# SCH_A320-MCDU-SMD_2024-02-10.net
KiCad netlist of a schematic drawn in EasyEDA
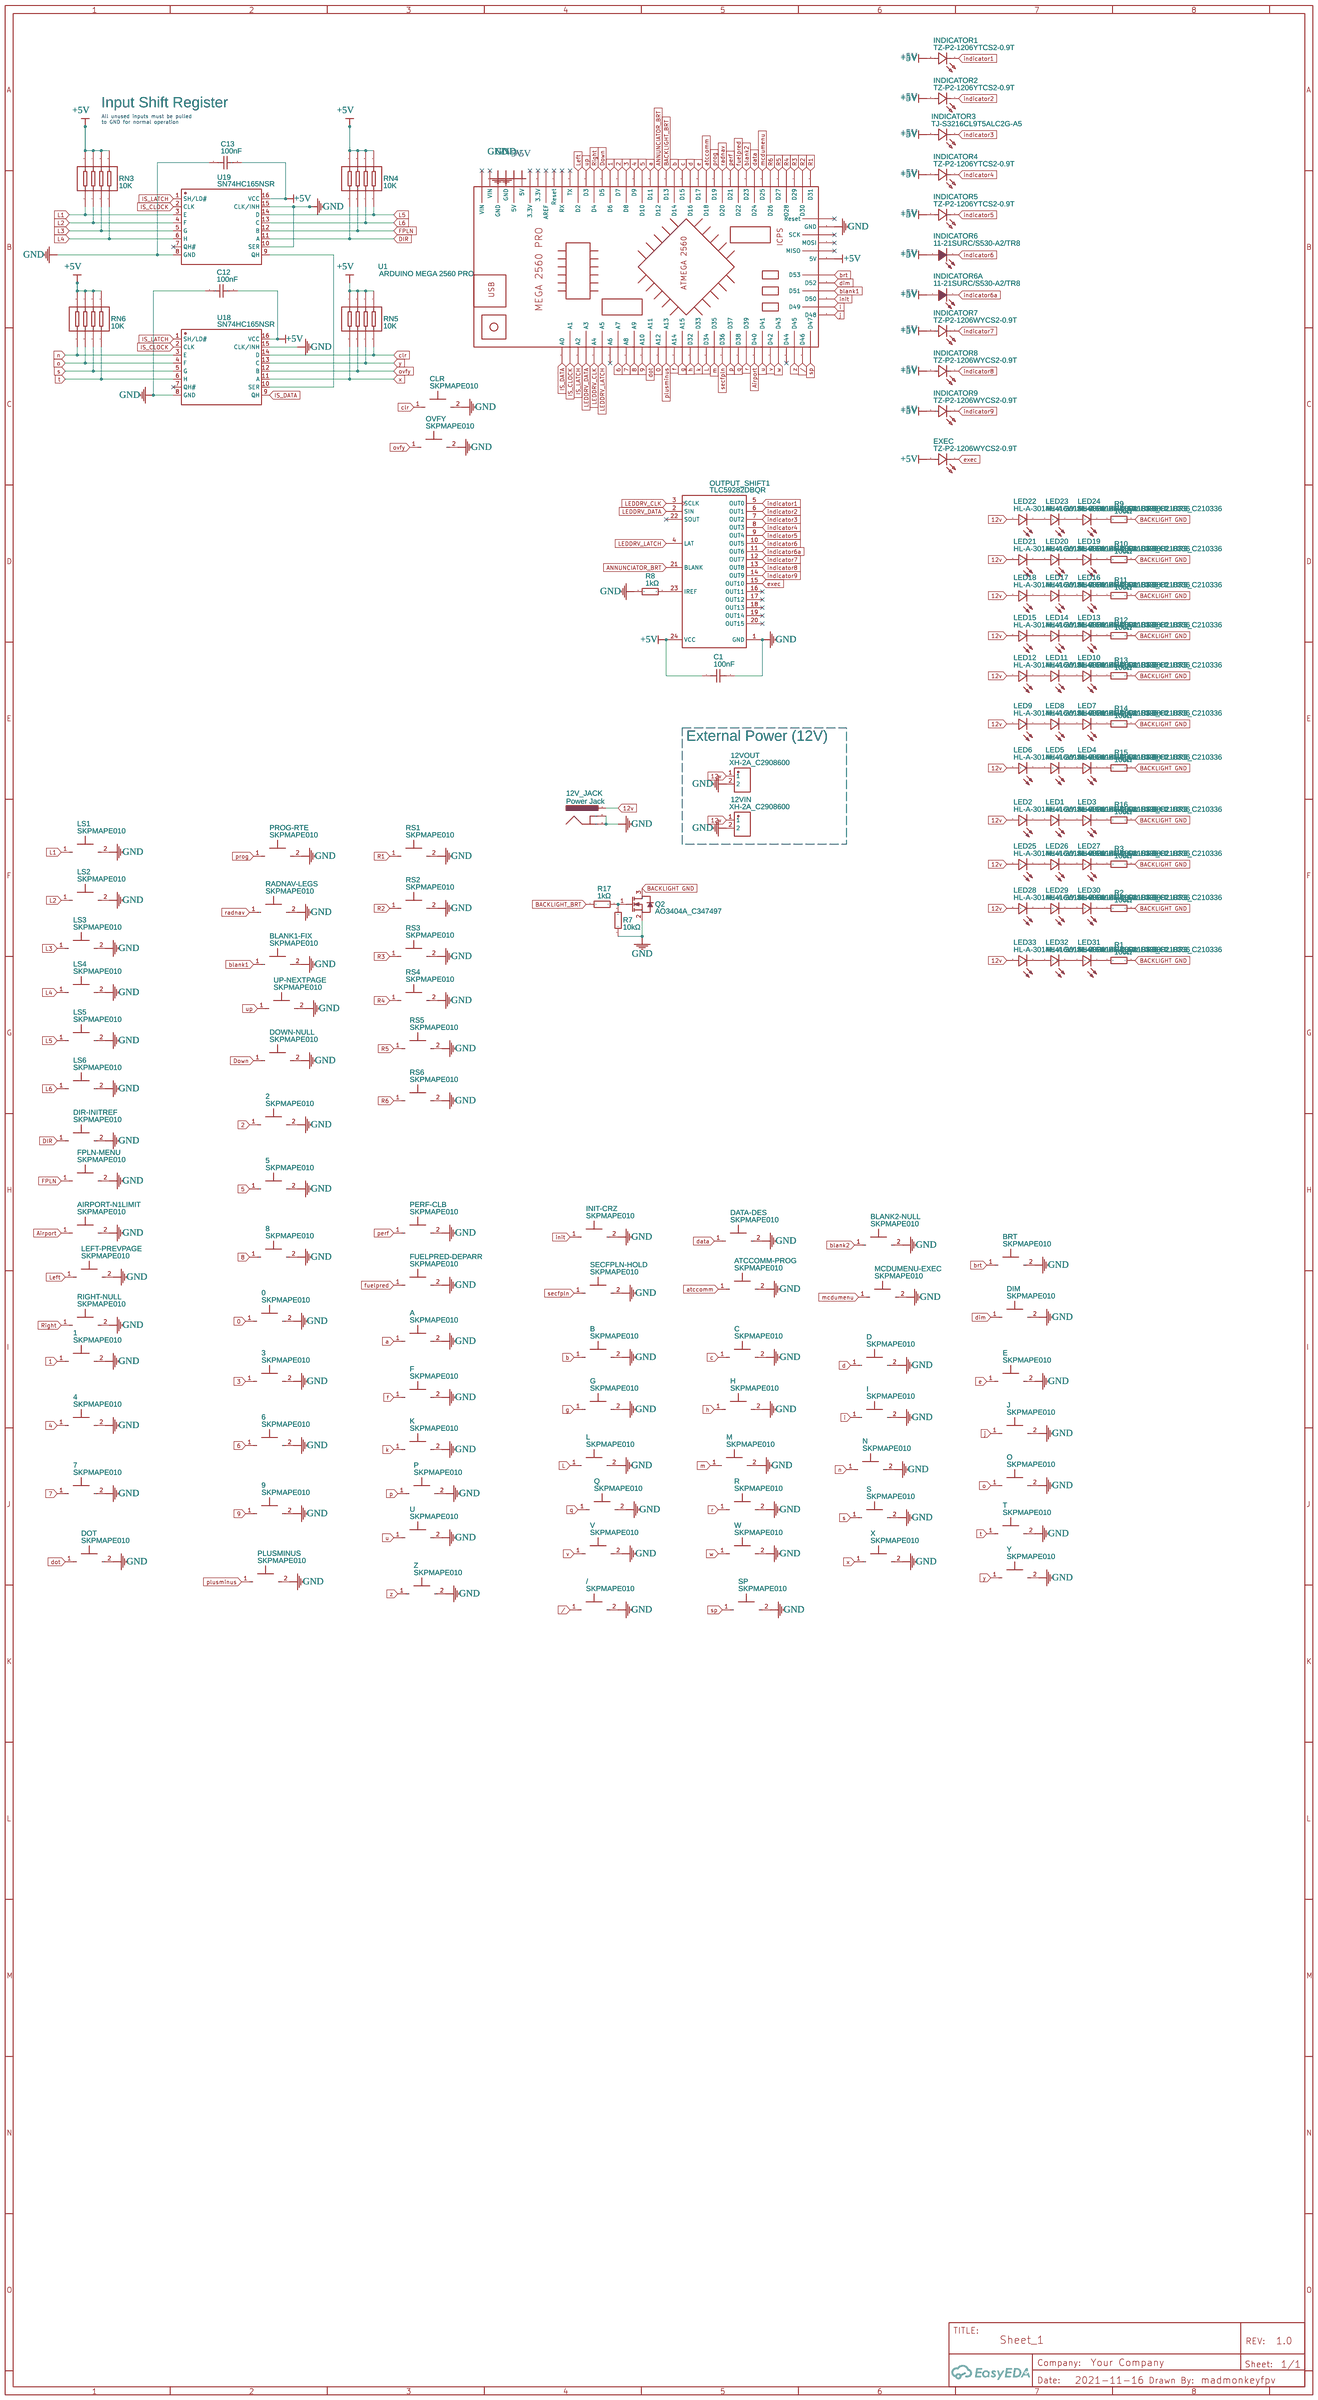
[diagram p0: schematic sheet]

(export (version "E")
  (design (tool "Eeschema 10.0.6"))
  (components
    (comp (ref "/")
      (value "SKPMAPE010")
      (fields (field (name "Manufacturer") "ALPS"))
      (libsource (lib "") (part "SKPMAPE010_46"))
    )
    (comp (ref "0")
      (value "SKPMAPE010")
      (fields (field (name "Manufacturer") "ALPS"))
      (libsource (lib "") (part "SKPMAPE010_12"))
    )
    (comp (ref "1")
      (value "SKPMAPE010")
      (fields (field (name "Manufacturer") "ALPS"))
      (libsource (lib "") (part "SKPMAPE010_12"))
    )
    (comp (ref "2")
      (value "SKPMAPE010")
      (fields (field (name "Manufacturer") "ALPS"))
      (libsource (lib "") (part "SKPMAPE010_12"))
    )
    (comp (ref "3")
      (value "SKPMAPE010")
      (fields (field (name "Manufacturer") "ALPS"))
      (libsource (lib "") (part "SKPMAPE010_12"))
    )
    (comp (ref "4")
      (value "SKPMAPE010")
      (fields (field (name "Manufacturer") "ALPS"))
      (libsource (lib "") (part "SKPMAPE010_12"))
    )
    (comp (ref "5")
      (value "SKPMAPE010")
      (fields (field (name "Manufacturer") "ALPS"))
      (libsource (lib "") (part "SKPMAPE010_12"))
    )
    (comp (ref "6")
      (value "SKPMAPE010")
      (fields (field (name "Manufacturer") "ALPS"))
      (libsource (lib "") (part "SKPMAPE010_12"))
    )
    (comp (ref "7")
      (value "SKPMAPE010")
      (fields (field (name "Manufacturer") "ALPS"))
      (libsource (lib "") (part "SKPMAPE010_12"))
    )
    (comp (ref "8")
      (value "SKPMAPE010")
      (fields (field (name "Manufacturer") "ALPS"))
      (libsource (lib "") (part "SKPMAPE010_12"))
    )
    (comp (ref "9")
      (value "SKPMAPE010")
      (fields (field (name "Manufacturer") "ALPS"))
      (libsource (lib "") (part "SKPMAPE010_12"))
    )
    (comp (ref "12VIN")
      (value "XH-2A_C2908600")
      (fields (field (name "Manufacturer Part") "XH-2A") (field (name "Manufacturer") "HCTL(华灿天禄)"))
      (libsource (lib "") (part "XH-2A_C2908600_1"))
    )
    (comp (ref "12VOUT")
      (value "XH-2A_C2908600")
      (fields (field (name "Manufacturer Part") "XH-2A") (field (name "Manufacturer") "HCTL(华灿天禄)"))
      (libsource (lib "") (part "XH-2A_C2908600"))
    )
    (comp (ref "12V_JACK")
      (value "Power Jack")
      (fields (field (name "Manufacturer") "Wealth Metal"))
      (libsource (lib "") (part "POWER_JACK"))
    )
    (comp (ref "A")
      (value "SKPMAPE010")
      (fields (field (name "Manufacturer Part") "KSC241JLFS") (field (name "Manufacturer") "C&K"))
      (libsource (lib "") (part "Unknown_0_-806"))
    )
    (comp (ref "AIRPORT-N1LIMIT")
      (value "SKPMAPE010")
      (fields (field (name "Manufacturer") "ALPS"))
      (libsource (lib "") (part "SKPMAPE010_50"))
    )
    (comp (ref "ATCCOMM-PROG")
      (value "SKPMAPE010")
      (fields (field (name "Manufacturer") "ALPS"))
      (libsource (lib "") (part "SKPMAPE010_43"))
    )
    (comp (ref "B")
      (value "SKPMAPE010")
      (fields (field (name "Manufacturer") "ALPS"))
      (libsource (lib "") (part "SKPMAPE010_31"))
    )
    (comp (ref "BLANK1-FIX")
      (value "SKPMAPE010")
      (fields (field (name "Manufacturer") "ALPS"))
      (libsource (lib "") (part "SKPMAPE010_4"))
    )
    (comp (ref "BLANK2-NULL")
      (value "SKPMAPE010")
      (fields (field (name "Manufacturer") "ALPS"))
      (libsource (lib "") (part "SKPMAPE010_39"))
    )
    (comp (ref "BRT")
      (value "SKPMAPE010")
      (fields (field (name "Manufacturer") "ALPS"))
      (libsource (lib "") (part "SKPMAPE010_25"))
    )
    (comp (ref "C")
      (value "SKPMAPE010")
      (fields (field (name "Manufacturer") "ALPS"))
      (libsource (lib "") (part "SKPMAPE010_40"))
    )
    (comp (ref "C1")
      (value "100nF")
      (fields (field (name "Manufacturer Part") "CC0603KRX7R9BB104") (field (name "Manufacturer") "YAGEO"))
      (libsource (lib "") (part "CC0603KRX7R9BB104"))
    )
    (comp (ref "C12")
      (value "100nF")
      (fields (field (name "Manufacturer Part") "CC0603KRX7R9BB104") (field (name "Manufacturer") "YAGEO"))
      (libsource (lib "") (part "CC0603KRX7R9BB104"))
    )
    (comp (ref "C13")
      (value "100nF")
      (fields (field (name "Manufacturer Part") "CC0603KRX7R9BB104") (field (name "Manufacturer") "YAGEO"))
      (libsource (lib "") (part "CC0603KRX7R9BB104"))
    )
    (comp (ref "CLR")
      (value "SKPMAPE010")
      (fields (field (name "Manufacturer") "ALPS"))
      (libsource (lib "") (part "SKPMAPE010_34"))
    )
    (comp (ref "D")
      (value "SKPMAPE010")
      (fields (field (name "Manufacturer") "ALPS"))
      (libsource (lib "") (part "SKPMAPE010_32"))
    )
    (comp (ref "DATA-DES")
      (value "SKPMAPE010")
      (fields (field (name "Manufacturer") "ALPS"))
      (libsource (lib "") (part "SKPMAPE010_22"))
    )
    (comp (ref "DIM")
      (value "SKPMAPE010")
      (fields (field (name "Manufacturer") "ALPS"))
      (libsource (lib "") (part "SKPMAPE010_42"))
    )
    (comp (ref "DIR-INITREF")
      (value "SKPMAPE010")
      (fields (field (name "Manufacturer") "ALPS"))
      (libsource (lib "") (part "SKPMAPE010_14"))
    )
    (comp (ref "DOT")
      (value "SKPMAPE010")
      (fields (field (name "Manufacturer") "ALPS"))
      (libsource (lib "") (part "SKPMAPE010_2"))
    )
    (comp (ref "DOWN-NULL")
      (value "SKPMAPE010")
      (fields (field (name "Manufacturer") "ALPS"))
      (libsource (lib "") (part "SKPMAPE010_21"))
    )
    (comp (ref "E")
      (value "SKPMAPE010")
      (fields (field (name "Manufacturer") "ALPS"))
      (libsource (lib "") (part "SKPMAPE010_17"))
    )
    (comp (ref "EXEC")
      (value "TZ-P2-1206WYCS2-0.9T")
      (fields (field (name "Manufacturer") "TUOZHAN"))
      (libsource (lib "") (part "TZ-P2-1206WYCS2-0.9T"))
    )
    (comp (ref "F")
      (value "SKPMAPE010")
      (fields (field (name "Manufacturer") "ALPS"))
      (libsource (lib "") (part "SKPMAPE010_27"))
    )
    (comp (ref "FPLN-MENU")
      (value "SKPMAPE010")
      (fields (field (name "Manufacturer") "ALPS"))
      (libsource (lib "") (part "SKPMAPE010_20"))
    )
    (comp (ref "FUELPRED-DEPARR")
      (value "SKPMAPE010")
      (fields (field (name "Manufacturer") "ALPS"))
      (libsource (lib "") (part "SKPMAPE010_1"))
    )
    (comp (ref "G")
      (value "SKPMAPE010")
      (fields (field (name "Manufacturer") "ALPS"))
      (libsource (lib "") (part "SKPMAPE010_49"))
    )
    (comp (ref "H")
      (value "SKPMAPE010")
      (fields (field (name "Manufacturer") "ALPS"))
      (libsource (lib "") (part "SKPMAPE010_19"))
    )
    (comp (ref "I")
      (value "SKPMAPE010")
      (fields (field (name "Manufacturer") "ALPS"))
      (libsource (lib "") (part "SKPMAPE010_47"))
    )
    (comp (ref "INDICATOR1")
      (value "TZ-P2-1206YTCS2-0.9T")
      (fields (field (name "Manufacturer") "TUOZHAN"))
      (libsource (lib "") (part "TZ-P2-1206YTCS2-0.9T"))
    )
    (comp (ref "INDICATOR2")
      (value "TZ-P2-1206YTCS2-0.9T")
      (fields (field (name "Manufacturer") "TUOZHAN"))
      (libsource (lib "") (part "TZ-P2-1206YTCS2-0.9T"))
    )
    (comp (ref "INDICATOR3")
      (value "TJ-S3216CL9T5ALC2G-A5")
      (fields (field (name "Manufacturer") "TOGIALED"))
      (libsource (lib "") (part "TJ-S3216CL9T5ALC2G-A5"))
    )
    (comp (ref "INDICATOR4")
      (value "TZ-P2-1206YTCS2-0.9T")
      (fields (field (name "Manufacturer") "TUOZHAN"))
      (libsource (lib "") (part "TZ-P2-1206YTCS2-0.9T"))
    )
    (comp (ref "INDICATOR5")
      (value "TZ-P2-1206YTCS2-0.9T")
      (fields (field (name "Manufacturer") "TUOZHAN"))
      (libsource (lib "") (part "TZ-P2-1206YTCS2-0.9T"))
    )
    (comp (ref "INDICATOR6")
      (value "11-21SURC/S530-A2/TR8")
      (fields (field (name "Manufacturer") "Everlight Elec"))
      (libsource (lib "") (part "11-21SURC/S530-A2/TR8"))
    )
    (comp (ref "INDICATOR6A")
      (value "11-21SURC/S530-A2/TR8")
      (fields (field (name "Manufacturer") "Everlight Elec"))
      (libsource (lib "") (part "11-21SURC/S530-A2/TR8_1"))
    )
    (comp (ref "INDICATOR7")
      (value "TZ-P2-1206WYCS2-0.9T")
      (fields (field (name "Manufacturer") "TUOZHAN"))
      (libsource (lib "") (part "TZ-P2-1206WYCS2-0.9T_1"))
    )
    (comp (ref "INDICATOR8")
      (value "TZ-P2-1206WYCS2-0.9T")
      (fields (field (name "Manufacturer") "TUOZHAN"))
      (libsource (lib "") (part "TZ-P2-1206WYCS2-0.9T_1"))
    )
    (comp (ref "INDICATOR9")
      (value "TZ-P2-1206WYCS2-0.9T")
      (fields (field (name "Manufacturer") "TUOZHAN"))
      (libsource (lib "") (part "TZ-P2-1206WYCS2-0.9T_1"))
    )
    (comp (ref "INIT-CRZ")
      (value "SKPMAPE010")
      (fields (field (name "Manufacturer") "ALPS"))
      (libsource (lib "") (part "SKPMAPE010_7"))
    )
    (comp (ref "J")
      (value "SKPMAPE010")
      (fields (field (name "Manufacturer") "ALPS"))
      (libsource (lib "") (part "SKPMAPE010_37"))
    )
    (comp (ref "K")
      (value "SKPMAPE010")
      (fields (field (name "Manufacturer") "ALPS"))
      (libsource (lib "") (part "SKPMAPE010_8"))
    )
    (comp (ref "L")
      (value "SKPMAPE010")
      (fields (field (name "Manufacturer") "ALPS"))
      (libsource (lib "") (part "SKPMAPE010_48"))
    )
    (comp (ref "LED1")
      (value "HL-A-3014H416W-S1-08HL-HR3_C210336")
      (fields (field (name "Manufacturer") "Hongli Zhihui (HONGLITRONIC)"))
      (libsource (lib "") (part "HL-A-3014H416W-S1-08HL-HR3_C210336"))
    )
    (comp (ref "LED2")
      (value "HL-A-3014H416W-S1-08HL-HR3_C210336")
      (fields (field (name "Manufacturer") "Hongli Zhihui (HONGLITRONIC)"))
      (libsource (lib "") (part "HL-A-3014H416W-S1-08HL-HR3_C210336"))
    )
    (comp (ref "LED3")
      (value "HL-A-3014H416W-S1-08HL-HR3_C210336")
      (fields (field (name "Manufacturer") "Hongli Zhihui (HONGLITRONIC)"))
      (libsource (lib "") (part "HL-A-3014H416W-S1-08HL-HR3_C210336"))
    )
    (comp (ref "LED4")
      (value "HL-A-3014H416W-S1-08HL-HR3_C210336")
      (fields (field (name "Manufacturer") "Hongli Zhihui (HONGLITRONIC)"))
      (libsource (lib "") (part "HL-A-3014H416W-S1-08HL-HR3_C210336"))
    )
    (comp (ref "LED5")
      (value "HL-A-3014H416W-S1-08HL-HR3_C210336")
      (fields (field (name "Manufacturer") "Hongli Zhihui (HONGLITRONIC)"))
      (libsource (lib "") (part "HL-A-3014H416W-S1-08HL-HR3_C210336"))
    )
    (comp (ref "LED6")
      (value "HL-A-3014H416W-S1-08HL-HR3_C210336")
      (fields (field (name "Manufacturer") "Hongli Zhihui (HONGLITRONIC)"))
      (libsource (lib "") (part "HL-A-3014H416W-S1-08HL-HR3_C210336"))
    )
    (comp (ref "LED7")
      (value "HL-A-3014H416W-S1-08HL-HR3_C210336")
      (fields (field (name "Manufacturer") "Hongli Zhihui (HONGLITRONIC)"))
      (libsource (lib "") (part "HL-A-3014H416W-S1-08HL-HR3_C210336"))
    )
    (comp (ref "LED8")
      (value "HL-A-3014H416W-S1-08HL-HR3_C210336")
      (fields (field (name "Manufacturer") "Hongli Zhihui (HONGLITRONIC)"))
      (libsource (lib "") (part "HL-A-3014H416W-S1-08HL-HR3_C210336"))
    )
    (comp (ref "LED9")
      (value "HL-A-3014H416W-S1-08HL-HR3_C210336")
      (fields (field (name "Manufacturer") "Hongli Zhihui (HONGLITRONIC)"))
      (libsource (lib "") (part "HL-A-3014H416W-S1-08HL-HR3_C210336"))
    )
    (comp (ref "LED10")
      (value "HL-A-3014H416W-S1-08HL-HR3_C210336")
      (fields (field (name "Manufacturer") "Hongli Zhihui (HONGLITRONIC)"))
      (libsource (lib "") (part "HL-A-3014H416W-S1-08HL-HR3_C210336"))
    )
    (comp (ref "LED11")
      (value "HL-A-3014H416W-S1-08HL-HR3_C210336")
      (fields (field (name "Manufacturer") "Hongli Zhihui (HONGLITRONIC)"))
      (libsource (lib "") (part "HL-A-3014H416W-S1-08HL-HR3_C210336"))
    )
    (comp (ref "LED12")
      (value "HL-A-3014H416W-S1-08HL-HR3_C210336")
      (fields (field (name "Manufacturer") "Hongli Zhihui (HONGLITRONIC)"))
      (libsource (lib "") (part "HL-A-3014H416W-S1-08HL-HR3_C210336"))
    )
    (comp (ref "LED13")
      (value "HL-A-3014H416W-S1-08HL-HR3_C210336")
      (fields (field (name "Manufacturer") "Hongli Zhihui (HONGLITRONIC)"))
      (libsource (lib "") (part "HL-A-3014H416W-S1-08HL-HR3_C210336"))
    )
    (comp (ref "LED14")
      (value "HL-A-3014H416W-S1-08HL-HR3_C210336")
      (fields (field (name "Manufacturer") "Hongli Zhihui (HONGLITRONIC)"))
      (libsource (lib "") (part "HL-A-3014H416W-S1-08HL-HR3_C210336"))
    )
    (comp (ref "LED15")
      (value "HL-A-3014H416W-S1-08HL-HR3_C210336")
      (fields (field (name "Manufacturer") "Hongli Zhihui (HONGLITRONIC)"))
      (libsource (lib "") (part "HL-A-3014H416W-S1-08HL-HR3_C210336"))
    )
    (comp (ref "LED16")
      (value "HL-A-3014H416W-S1-08HL-HR3_C210336")
      (fields (field (name "Manufacturer") "Hongli Zhihui (HONGLITRONIC)"))
      (libsource (lib "") (part "HL-A-3014H416W-S1-08HL-HR3_C210336"))
    )
    (comp (ref "LED17")
      (value "HL-A-3014H416W-S1-08HL-HR3_C210336")
      (fields (field (name "Manufacturer") "Hongli Zhihui (HONGLITRONIC)"))
      (libsource (lib "") (part "HL-A-3014H416W-S1-08HL-HR3_C210336"))
    )
    (comp (ref "LED18")
      (value "HL-A-3014H416W-S1-08HL-HR3_C210336")
      (fields (field (name "Manufacturer") "Hongli Zhihui (HONGLITRONIC)"))
      (libsource (lib "") (part "HL-A-3014H416W-S1-08HL-HR3_C210336"))
    )
    (comp (ref "LED19")
      (value "HL-A-3014H416W-S1-08HL-HR3_C210336")
      (fields (field (name "Manufacturer") "Hongli Zhihui (HONGLITRONIC)"))
      (libsource (lib "") (part "HL-A-3014H416W-S1-08HL-HR3_C210336"))
    )
    (comp (ref "LED20")
      (value "HL-A-3014H416W-S1-08HL-HR3_C210336")
      (fields (field (name "Manufacturer") "Hongli Zhihui (HONGLITRONIC)"))
      (libsource (lib "") (part "HL-A-3014H416W-S1-08HL-HR3_C210336"))
    )
    (comp (ref "LED21")
      (value "HL-A-3014H416W-S1-08HL-HR3_C210336")
      (fields (field (name "Manufacturer") "Hongli Zhihui (HONGLITRONIC)"))
      (libsource (lib "") (part "HL-A-3014H416W-S1-08HL-HR3_C210336"))
    )
    (comp (ref "LED22")
      (value "HL-A-3014H416W-S1-08HL-HR3_C210336")
      (fields (field (name "Manufacturer") "Hongli Zhihui (HONGLITRONIC)"))
      (libsource (lib "") (part "HL-A-3014H416W-S1-08HL-HR3_C210336"))
    )
    (comp (ref "LED23")
      (value "HL-A-3014H416W-S1-08HL-HR3_C210336")
      (fields (field (name "Manufacturer") "Hongli Zhihui (HONGLITRONIC)"))
      (libsource (lib "") (part "HL-A-3014H416W-S1-08HL-HR3_C210336"))
    )
    (comp (ref "LED24")
      (value "HL-A-3014H416W-S1-08HL-HR3_C210336")
      (fields (field (name "Manufacturer") "Hongli Zhihui (HONGLITRONIC)"))
      (libsource (lib "") (part "HL-A-3014H416W-S1-08HL-HR3_C210336"))
    )
    (comp (ref "LED25")
      (value "HL-A-3014H416W-S1-08HL-HR3_C210336")
      (fields (field (name "Manufacturer") "Hongli Zhihui (HONGLITRONIC)"))
      (libsource (lib "") (part "HL-A-3014H416W-S1-08HL-HR3_C210336"))
    )
    (comp (ref "LED26")
      (value "HL-A-3014H416W-S1-08HL-HR3_C210336")
      (fields (field (name "Manufacturer") "Hongli Zhihui (HONGLITRONIC)"))
      (libsource (lib "") (part "HL-A-3014H416W-S1-08HL-HR3_C210336"))
    )
    (comp (ref "LED27")
      (value "HL-A-3014H416W-S1-08HL-HR3_C210336")
      (fields (field (name "Manufacturer") "Hongli Zhihui (HONGLITRONIC)"))
      (libsource (lib "") (part "HL-A-3014H416W-S1-08HL-HR3_C210336"))
    )
    (comp (ref "LED28")
      (value "HL-A-3014H416W-S1-08HL-HR3_C210336")
      (fields (field (name "Manufacturer") "Hongli Zhihui (HONGLITRONIC)"))
      (libsource (lib "") (part "HL-A-3014H416W-S1-08HL-HR3_C210336"))
    )
    (comp (ref "LED29")
      (value "HL-A-3014H416W-S1-08HL-HR3_C210336")
      (fields (field (name "Manufacturer") "Hongli Zhihui (HONGLITRONIC)"))
      (libsource (lib "") (part "HL-A-3014H416W-S1-08HL-HR3_C210336"))
    )
    (comp (ref "LED30")
      (value "HL-A-3014H416W-S1-08HL-HR3_C210336")
      (fields (field (name "Manufacturer") "Hongli Zhihui (HONGLITRONIC)"))
      (libsource (lib "") (part "HL-A-3014H416W-S1-08HL-HR3_C210336"))
    )
    (comp (ref "LED31")
      (value "HL-A-3014H416W-S1-08HL-HR3_C210336")
      (fields (field (name "Manufacturer") "Hongli Zhihui (HONGLITRONIC)"))
      (libsource (lib "") (part "HL-A-3014H416W-S1-08HL-HR3_C210336"))
    )
    (comp (ref "LED32")
      (value "HL-A-3014H416W-S1-08HL-HR3_C210336")
      (fields (field (name "Manufacturer") "Hongli Zhihui (HONGLITRONIC)"))
      (libsource (lib "") (part "HL-A-3014H416W-S1-08HL-HR3_C210336"))
    )
    (comp (ref "LED33")
      (value "HL-A-3014H416W-S1-08HL-HR3_C210336")
      (fields (field (name "Manufacturer") "Hongli Zhihui (HONGLITRONIC)"))
      (libsource (lib "") (part "HL-A-3014H416W-S1-08HL-HR3_C210336"))
    )
    (comp (ref "LEFT-PREVPAGE")
      (value "SKPMAPE010")
      (fields (field (name "Manufacturer") "ALPS"))
      (libsource (lib "") (part "SKPMAPE010_36"))
    )
    (comp (ref "LS1")
      (value "SKPMAPE010")
      (fields (field (name "Manufacturer") "ALPS"))
      (libsource (lib "") (part "SKPMAPE010_16"))
    )
    (comp (ref "LS2")
      (value "SKPMAPE010")
      (fields (field (name "Manufacturer") "ALPS"))
      (libsource (lib "") (part "SKPMAPE010_16"))
    )
    (comp (ref "LS3")
      (value "SKPMAPE010")
      (fields (field (name "Manufacturer") "ALPS"))
      (libsource (lib "") (part "SKPMAPE010_16"))
    )
    (comp (ref "LS4")
      (value "SKPMAPE010")
      (fields (field (name "Manufacturer") "ALPS"))
      (libsource (lib "") (part "SKPMAPE010_16"))
    )
    (comp (ref "LS5")
      (value "SKPMAPE010")
      (fields (field (name "Manufacturer") "ALPS"))
      (libsource (lib "") (part "SKPMAPE010_16"))
    )
    (comp (ref "LS6")
      (value "SKPMAPE010")
      (fields (field (name "Manufacturer") "ALPS"))
      (libsource (lib "") (part "SKPMAPE010_16"))
    )
    (comp (ref "M")
      (value "SKPMAPE010")
      (fields (field (name "Manufacturer") "ALPS"))
      (libsource (lib "") (part "SKPMAPE010_11"))
    )
    (comp (ref "MCDUMENU-EXEC")
      (value "SKPMAPE010")
      (fields (field (name "Manufacturer") "ALPS"))
      (libsource (lib "") (part "SKPMAPE010_44"))
    )
    (comp (ref "N")
      (value "SKPMAPE010")
      (fields (field (name "Manufacturer") "ALPS"))
      (libsource (lib "") (part "SKPMAPE010_18"))
    )
    (comp (ref "O")
      (value "SKPMAPE010")
      (fields (field (name "Manufacturer") "ALPS"))
      (libsource (lib "") (part "SKPMAPE010_51"))
    )
    (comp (ref "OUTPUT_SHIFT1")
      (value "TLC59282DBQR")
      (fields (field (name "Manufacturer") "TI(德州仪器)"))
      (libsource (lib "") (part "TLC59282DBQR"))
    )
    (comp (ref "OVFY")
      (value "SKPMAPE010")
      (fields (field (name "Manufacturer") "ALPS"))
      (libsource (lib "") (part "SKPMAPE010"))
    )
    (comp (ref "P")
      (value "SKPMAPE010")
      (fields (field (name "Manufacturer") "ALPS"))
      (libsource (lib "") (part "SKPMAPE010_38"))
    )
    (comp (ref "PERF-CLB")
      (value "SKPMAPE010")
      (fields (field (name "Manufacturer") "ALPS"))
      (libsource (lib "") (part "SKPMAPE010_10"))
    )
    (comp (ref "PLUSMINUS")
      (value "SKPMAPE010")
      (fields (field (name "Manufacturer") "ALPS"))
      (libsource (lib "") (part "SKPMAPE010_33"))
    )
    (comp (ref "PROG-RTE")
      (value "SKPMAPE010")
      (fields (field (name "Manufacturer") "ALPS"))
      (libsource (lib "") (part "SKPMAPE010_3"))
    )
    (comp (ref "Q")
      (value "SKPMAPE010")
      (fields (field (name "Manufacturer") "ALPS"))
      (libsource (lib "") (part "SKPMAPE010_45"))
    )
    (comp (ref "Q2")
      (value "AO3404A_C347497")
      (fields
        (field (name "Manufacturer Part") "AO3404A")
        (field (name "Manufacturer") "Youtai Semiconductor Co., Ltd.")
      )
      (libsource (lib "") (part "AO3404A_C347497"))
    )
    (comp (ref "R")
      (value "SKPMAPE010")
      (fields (field (name "Manufacturer") "ALPS"))
      (libsource (lib "") (part "SKPMAPE010_29"))
    )
    (comp (ref "R1")
      (value "100Ω")
      (fields (field (name "Manufacturer Part") "1206W4F1000T5E") (field (name "Manufacturer") "UniOhm"))
      (libsource (lib "") (part "1206W4F1000T5E"))
    )
    (comp (ref "R2")
      (value "100Ω")
      (fields (field (name "Manufacturer Part") "1206W4F1000T5E") (field (name "Manufacturer") "UniOhm"))
      (libsource (lib "") (part "1206W4F1000T5E"))
    )
    (comp (ref "R3")
      (value "100Ω")
      (fields (field (name "Manufacturer Part") "1206W4F1000T5E") (field (name "Manufacturer") "UniOhm"))
      (libsource (lib "") (part "1206W4F1000T5E"))
    )
    (comp (ref "R7")
      (value "10kΩ")
      (fields (field (name "Manufacturer Part") "1206W4F1002T5E") (field (name "Manufacturer") "UniOhm"))
      (libsource (lib "") (part "1206W4F1002T5E"))
    )
    (comp (ref "R8")
      (value "1kΩ")
      (fields (field (name "Manufacturer Part") "1206W4F1001T5E") (field (name "Manufacturer") "UniOhm"))
      (libsource (lib "") (part "1206W4F1001T5E"))
    )
    (comp (ref "R9")
      (value "100Ω")
      (fields (field (name "Manufacturer Part") "1206W4F1000T5E") (field (name "Manufacturer") "UniOhm"))
      (libsource (lib "") (part "1206W4F1000T5E"))
    )
    (comp (ref "R10")
      (value "100Ω")
      (fields (field (name "Manufacturer Part") "1206W4F1000T5E") (field (name "Manufacturer") "UniOhm"))
      (libsource (lib "") (part "1206W4F1000T5E"))
    )
    (comp (ref "R11")
      (value "100Ω")
      (fields (field (name "Manufacturer Part") "1206W4F1000T5E") (field (name "Manufacturer") "UniOhm"))
      (libsource (lib "") (part "1206W4F1000T5E"))
    )
    (comp (ref "R12")
      (value "100Ω")
      (fields (field (name "Manufacturer Part") "1206W4F1000T5E") (field (name "Manufacturer") "UniOhm"))
      (libsource (lib "") (part "1206W4F1000T5E"))
    )
    (comp (ref "R13")
      (value "100Ω")
      (fields (field (name "Manufacturer Part") "1206W4F1000T5E") (field (name "Manufacturer") "UniOhm"))
      (libsource (lib "") (part "1206W4F1000T5E"))
    )
    (comp (ref "R14")
      (value "100Ω")
      (fields (field (name "Manufacturer Part") "1206W4F1000T5E") (field (name "Manufacturer") "UniOhm"))
      (libsource (lib "") (part "1206W4F1000T5E"))
    )
    (comp (ref "R15")
      (value "100Ω")
      (fields (field (name "Manufacturer Part") "1206W4F1000T5E") (field (name "Manufacturer") "UniOhm"))
      (libsource (lib "") (part "1206W4F1000T5E"))
    )
    (comp (ref "R16")
      (value "100Ω")
      (fields (field (name "Manufacturer Part") "1206W4F1000T5E") (field (name "Manufacturer") "UniOhm"))
      (libsource (lib "") (part "1206W4F1000T5E"))
    )
    (comp (ref "R17")
      (value "1kΩ")
      (fields (field (name "Manufacturer Part") "1206W4F1001T5E") (field (name "Manufacturer") "UniOhm"))
      (libsource (lib "") (part "1206W4F1001T5E_1"))
    )
    (comp (ref "RADNAV-LEGS")
      (value "SKPMAPE010")
      (fields (field (name "Manufacturer") "ALPS"))
      (libsource (lib "") (part "SKPMAPE010_41"))
    )
    (comp (ref "RIGHT-NULL")
      (value "SKPMAPE010")
      (fields (field (name "Manufacturer") "ALPS"))
      (libsource (lib "") (part "SKPMAPE010_15"))
    )
    (comp (ref "RN3")
      (value "10K")
      (fields (field (name "Manufacturer Part") "YC164-FR-0710KL") (field (name "Manufacturer") "YAGEO"))
      (libsource (lib "") (part "YC164-FR-0710KL"))
    )
    (comp (ref "RN4")
      (value "10K")
      (fields (field (name "Manufacturer Part") "YC164-FR-0710KL") (field (name "Manufacturer") "YAGEO"))
      (libsource (lib "") (part "YC164-FR-0710KL_1"))
    )
    (comp (ref "RN5")
      (value "10K")
      (fields (field (name "Manufacturer Part") "YC164-FR-0710KL") (field (name "Manufacturer") "YAGEO"))
      (libsource (lib "") (part "YC164-FR-0710KL_1"))
    )
    (comp (ref "RN6")
      (value "10K")
      (fields (field (name "Manufacturer Part") "YC164-FR-0710KL") (field (name "Manufacturer") "YAGEO"))
      (libsource (lib "") (part "YC164-FR-0710KL"))
    )
    (comp (ref "RS1")
      (value "SKPMAPE010")
      (fields (field (name "Manufacturer") "ALPS"))
      (libsource (lib "") (part "SKPMAPE010_9"))
    )
    (comp (ref "RS2")
      (value "SKPMAPE010")
      (fields (field (name "Manufacturer") "ALPS"))
      (libsource (lib "") (part "SKPMAPE010_9"))
    )
    (comp (ref "RS3")
      (value "SKPMAPE010")
      (fields (field (name "Manufacturer") "ALPS"))
      (libsource (lib "") (part "SKPMAPE010_9"))
    )
    (comp (ref "RS4")
      (value "SKPMAPE010")
      (fields (field (name "Manufacturer") "ALPS"))
      (libsource (lib "") (part "SKPMAPE010_9"))
    )
    (comp (ref "RS5")
      (value "SKPMAPE010")
      (fields (field (name "Manufacturer") "ALPS"))
      (libsource (lib "") (part "SKPMAPE010_9"))
    )
    (comp (ref "RS6")
      (value "SKPMAPE010")
      (fields (field (name "Manufacturer") "ALPS"))
      (libsource (lib "") (part "SKPMAPE010_9"))
    )
    (comp (ref "S")
      (value "SKPMAPE010")
      (fields (field (name "Manufacturer") "ALPS"))
      (libsource (lib "") (part "SKPMAPE010_5"))
    )
    (comp (ref "SECFPLN-HOLD")
      (value "SKPMAPE010")
      (fields (field (name "Manufacturer") "ALPS"))
      (libsource (lib "") (part "SKPMAPE010_52"))
    )
    (comp (ref "SP")
      (value "SKPMAPE010")
      (fields (field (name "Manufacturer") "ALPS"))
      (libsource (lib "") (part "SKPMAPE010_26"))
    )
    (comp (ref "T")
      (value "SKPMAPE010")
      (fields (field (name "Manufacturer") "ALPS"))
      (libsource (lib "") (part "SKPMAPE010_13"))
    )
    (comp (ref "U")
      (value "SKPMAPE010")
      (fields (field (name "Manufacturer") "ALPS"))
      (libsource (lib "") (part "SKPMAPE010_53"))
    )
    (comp (ref "U1")
      (value "ARDUINO MEGA 2560 PRO")
      (fields (field (name "Manufacturer Part") "Arduino Mega 2560 Pro Mini"))
      (libsource (lib "") (part "ARDUINO MEGA 2560 PRO"))
    )
    (comp (ref "U18")
      (value "SN74HC165NSR")
      (fields (field (name "Manufacturer") "TI"))
      (libsource (lib "") (part "SN74HC165NSR"))
    )
    (comp (ref "U19")
      (value "SN74HC165NSR")
      (fields (field (name "Manufacturer") "TI"))
      (libsource (lib "") (part "SN74HC165NSR"))
    )
    (comp (ref "UP-NEXTPAGE")
      (value "SKPMAPE010")
      (fields (field (name "Manufacturer") "ALPS"))
      (libsource (lib "") (part "SKPMAPE010_24"))
    )
    (comp (ref "V")
      (value "SKPMAPE010")
      (fields (field (name "Manufacturer") "ALPS"))
      (libsource (lib "") (part "SKPMAPE010_30"))
    )
    (comp (ref "W")
      (value "SKPMAPE010")
      (fields (field (name "Manufacturer") "ALPS"))
      (libsource (lib "") (part "SKPMAPE010_23"))
    )
    (comp (ref "X")
      (value "SKPMAPE010")
      (fields (field (name "Manufacturer") "ALPS"))
      (libsource (lib "") (part "SKPMAPE010_28"))
    )
    (comp (ref "Y")
      (value "SKPMAPE010")
      (fields (field (name "Manufacturer") "ALPS"))
      (libsource (lib "") (part "SKPMAPE010_6"))
    )
    (comp (ref "Z")
      (value "SKPMAPE010")
      (fields (field (name "Manufacturer") "ALPS"))
      (libsource (lib "") (part "SKPMAPE010_54"))
    )
  )
  (nets
    (net (code "1") (name "+5V") (class "Default")
      (node (ref "C1") (pin "1") (pinfunction "1_1") (pintype "unspecified"))
      (node (ref "C12") (pin "2") (pinfunction "2_2") (pintype "unspecified"))
      (node (ref "C13") (pin "2") (pinfunction "2_2") (pintype "unspecified"))
      (node (ref "EXEC") (pin "2") (pinfunction "A_2") (pintype "unspecified"))
      (node (ref "INDICATOR1") (pin "2") (pinfunction "A_2") (pintype "unspecified"))
      (node (ref "INDICATOR2") (pin "2") (pinfunction "A_2") (pintype "unspecified"))
      (node (ref "INDICATOR3") (pin "2") (pinfunction "A_2") (pintype "unspecified"))
      (node (ref "INDICATOR4") (pin "2") (pinfunction "A_2") (pintype "unspecified"))
      (node (ref "INDICATOR5") (pin "2") (pinfunction "A_2") (pintype "unspecified"))
      (node (ref "INDICATOR6") (pin "1") (pinfunction "A_1") (pintype "unspecified"))
      (node (ref "INDICATOR6A") (pin "1") (pinfunction "A_1") (pintype "unspecified"))
      (node (ref "INDICATOR7") (pin "2") (pinfunction "A_2") (pintype "unspecified"))
      (node (ref "INDICATOR8") (pin "2") (pinfunction "A_2") (pintype "unspecified"))
      (node (ref "INDICATOR9") (pin "2") (pinfunction "A_2") (pintype "unspecified"))
      (node (ref "OUTPUT_SHIFT1") (pin "24") (pinfunction "VCC_24") (pintype "passive"))
      (node (ref "RN3") (pin "5") (pinfunction "5_5") (pintype "input"))
      (node (ref "RN3") (pin "6") (pinfunction "6_6") (pintype "input"))
      (node (ref "RN3") (pin "7") (pinfunction "7_7") (pintype "input"))
      (node (ref "RN3") (pin "8") (pinfunction "8_8") (pintype "input"))
      (node (ref "RN4") (pin "1") (pinfunction "1_1") (pintype "input"))
      (node (ref "RN4") (pin "2") (pinfunction "2_2") (pintype "input"))
      (node (ref "RN4") (pin "3") (pinfunction "3_3") (pintype "input"))
      (node (ref "RN4") (pin "4") (pinfunction "4_4") (pintype "input"))
      (node (ref "RN5") (pin "1") (pinfunction "1_1") (pintype "input"))
      (node (ref "RN5") (pin "2") (pinfunction "2_2") (pintype "input"))
      (node (ref "RN5") (pin "3") (pinfunction "3_3") (pintype "input"))
      (node (ref "RN5") (pin "4") (pinfunction "4_4") (pintype "input"))
      (node (ref "RN6") (pin "5") (pinfunction "5_5") (pintype "input"))
      (node (ref "RN6") (pin "6") (pinfunction "6_6") (pintype "input"))
      (node (ref "RN6") (pin "7") (pinfunction "7_7") (pintype "input"))
      (node (ref "RN6") (pin "8") (pinfunction "8_8") (pintype "input"))
      (node (ref "U1") (pin "39") (pinfunction "5V_39") (pintype "unspecified"))
      (node (ref "U1") (pin "81") (pinfunction "5V_81") (pintype "unspecified"))
      (node (ref "U1") (pin "82") (pinfunction "5V_82") (pintype "unspecified"))
      (node (ref "U18") (pin "16") (pinfunction "VCC_16") (pintype "unspecified"))
      (node (ref "U19") (pin "16") (pinfunction "VCC_16") (pintype "unspecified"))
    )
    (net (code "2") (name "0") (class "Default")
      (node (ref "0") (pin "1") (pinfunction "1_1") (pintype "input"))
      (node (ref "U1") (pin "13") (pinfunction "A12_13") (pintype "unspecified"))
    )
    (net (code "3") (name "1") (class "Default")
      (node (ref "1") (pin "1") (pinfunction "1_1") (pintype "input"))
      (node (ref "U1") (pin "70") (pinfunction "D6_70") (pintype "unspecified"))
    )
    (net (code "4") (name "2") (class "Default")
      (node (ref "2") (pin "1") (pinfunction "1_1") (pintype "input"))
      (node (ref "U1") (pin "69") (pinfunction "D7_69") (pintype "unspecified"))
    )
    (net (code "5") (name "3") (class "Default")
      (node (ref "3") (pin "1") (pinfunction "1_1") (pintype "input"))
      (node (ref "U1") (pin "68") (pinfunction "D8_68") (pintype "unspecified"))
    )
    (net (code "6") (name "4") (class "Default")
      (node (ref "4") (pin "1") (pinfunction "1_1") (pintype "input"))
      (node (ref "U1") (pin "67") (pinfunction "D9_67") (pintype "unspecified"))
    )
    (net (code "7") (name "5") (class "Default")
      (node (ref "5") (pin "1") (pinfunction "1_1") (pintype "input"))
      (node (ref "U1") (pin "66") (pinfunction "D10_66") (pintype "unspecified"))
    )
    (net (code "8") (name "6") (class "Default")
      (node (ref "6") (pin "1") (pinfunction "1_1") (pintype "input"))
      (node (ref "U1") (pin "8") (pinfunction "A7_8") (pintype "unspecified"))
    )
    (net (code "9") (name "7") (class "Default")
      (node (ref "7") (pin "1") (pinfunction "1_1") (pintype "input"))
      (node (ref "U1") (pin "9") (pinfunction "A8_9") (pintype "unspecified"))
    )
    (net (code "10") (name "8") (class "Default")
      (node (ref "8") (pin "1") (pinfunction "1_1") (pintype "input"))
      (node (ref "U1") (pin "10") (pinfunction "A9_10") (pintype "unspecified"))
    )
    (net (code "11") (name "9") (class "Default")
      (node (ref "9") (pin "1") (pinfunction "1_1") (pintype "input"))
      (node (ref "U1") (pin "11") (pinfunction "A10_11") (pintype "unspecified"))
    )
    (net (code "12") (name "12v") (class "Default")
      (node (ref "12VIN") (pin "1") (pinfunction "1_1") (pintype "unspecified"))
      (node (ref "12VOUT") (pin "1") (pinfunction "1_1") (pintype "unspecified"))
      (node (ref "12V_JACK") (pin "PWR") (pinfunction "PWR_PWR") (pintype "unspecified"))
      (node (ref "LED12") (pin "2") (pinfunction "2_2") (pintype "unspecified"))
      (node (ref "LED15") (pin "2") (pinfunction "2_2") (pintype "unspecified"))
      (node (ref "LED18") (pin "2") (pinfunction "2_2") (pintype "unspecified"))
      (node (ref "LED2") (pin "2") (pinfunction "2_2") (pintype "unspecified"))
      (node (ref "LED21") (pin "2") (pinfunction "2_2") (pintype "unspecified"))
      (node (ref "LED22") (pin "2") (pinfunction "2_2") (pintype "unspecified"))
      (node (ref "LED25") (pin "2") (pinfunction "2_2") (pintype "unspecified"))
      (node (ref "LED28") (pin "2") (pinfunction "2_2") (pintype "unspecified"))
      (node (ref "LED33") (pin "2") (pinfunction "2_2") (pintype "unspecified"))
      (node (ref "LED6") (pin "2") (pinfunction "2_2") (pintype "unspecified"))
      (node (ref "LED9") (pin "2") (pinfunction "2_2") (pintype "unspecified"))
    )
    (net (code "13") (name "ANNUNCIATOR_BRT") (class "Default")
      (node (ref "OUTPUT_SHIFT1") (pin "21") (pinfunction "BLANK_21") (pintype "unspecified"))
      (node (ref "U1") (pin "64") (pinfunction "D12_64") (pintype "unspecified"))
    )
    (net (code "14") (name "Airport") (class "Default")
      (node (ref "AIRPORT-N1LIMIT") (pin "1") (pinfunction "1_1") (pintype "input"))
      (node (ref "U1") (pin "25") (pinfunction "D40_25") (pintype "unspecified"))
    )
    (net (code "15") (name "BACKLIGHT GND") (class "Default")
      (node (ref "Q2") (pin "3") (pinfunction "D_3") (pintype "unspecified"))
      (node (ref "R1") (pin "2") (pinfunction "2_2") (pintype "input"))
      (node (ref "R10") (pin "2") (pinfunction "2_2") (pintype "input"))
      (node (ref "R11") (pin "2") (pinfunction "2_2") (pintype "input"))
      (node (ref "R12") (pin "2") (pinfunction "2_2") (pintype "input"))
      (node (ref "R13") (pin "2") (pinfunction "2_2") (pintype "input"))
      (node (ref "R14") (pin "2") (pinfunction "2_2") (pintype "input"))
      (node (ref "R15") (pin "2") (pinfunction "2_2") (pintype "input"))
      (node (ref "R16") (pin "2") (pinfunction "2_2") (pintype "input"))
      (node (ref "R2") (pin "2") (pinfunction "2_2") (pintype "input"))
      (node (ref "R3") (pin "2") (pinfunction "2_2") (pintype "input"))
      (node (ref "R9") (pin "2") (pinfunction "2_2") (pintype "input"))
    )
    (net (code "16") (name "BACKLIGHT_BRT") (class "Default")
      (node (ref "R17") (pin "1") (pinfunction "1_1") (pintype "input"))
      (node (ref "U1") (pin "63") (pinfunction "D13_63") (pintype "unspecified"))
    )
    (net (code "17") (name "DIR") (class "Default")
      (node (ref "DIR-INITREF") (pin "1") (pinfunction "1_1") (pintype "input"))
      (node (ref "RN4") (pin "5") (pinfunction "5_5") (pintype "input"))
      (node (ref "U19") (pin "11") (pinfunction "A_11") (pintype "unspecified"))
    )
    (net (code "18") (name "Down") (class "Default")
      (node (ref "DOWN-NULL") (pin "1") (pinfunction "1_1") (pintype "input"))
      (node (ref "U1") (pin "71") (pinfunction "D5_71") (pintype "unspecified"))
    )
    (net (code "19") (name "FPLN") (class "Default")
      (node (ref "FPLN-MENU") (pin "1") (pinfunction "1_1") (pintype "input"))
      (node (ref "RN4") (pin "6") (pinfunction "6_6") (pintype "input"))
      (node (ref "U19") (pin "12") (pinfunction "B_12") (pintype "unspecified"))
    )
    (net (code "20") (name "GND") (class "Default")
      (node (ref "/") (pin "2") (pinfunction "2_2") (pintype "input"))
      (node (ref "0") (pin "2") (pinfunction "2_2") (pintype "input"))
      (node (ref "1") (pin "2") (pinfunction "2_2") (pintype "input"))
      (node (ref "12VIN") (pin "2") (pinfunction "2_2") (pintype "unspecified"))
      (node (ref "12VOUT") (pin "2") (pinfunction "2_2") (pintype "unspecified"))
      (node (ref "12V_JACK") (pin "GND") (pinfunction "GND_GND") (pintype "unspecified"))
      (node (ref "12V_JACK") (pin "GNDBREAK") (pinfunction "GNDBREAK_GNDBREAK") (pintype "unspecified"))
      (node (ref "2") (pin "2") (pinfunction "2_2") (pintype "input"))
      (node (ref "3") (pin "2") (pinfunction "2_2") (pintype "input"))
      (node (ref "4") (pin "2") (pinfunction "2_2") (pintype "input"))
      (node (ref "5") (pin "2") (pinfunction "2_2") (pintype "input"))
      (node (ref "6") (pin "2") (pinfunction "2_2") (pintype "input"))
      (node (ref "7") (pin "2") (pinfunction "2_2") (pintype "input"))
      (node (ref "8") (pin "2") (pinfunction "2_2") (pintype "input"))
      (node (ref "9") (pin "2") (pinfunction "2_2") (pintype "input"))
      (node (ref "A") (pin "2") (pinfunction "2_2") (pintype "input"))
      (node (ref "AIRPORT-N1LIMIT") (pin "2") (pinfunction "2_2") (pintype "input"))
      (node (ref "ATCCOMM-PROG") (pin "2") (pinfunction "2_2") (pintype "input"))
      (node (ref "B") (pin "2") (pinfunction "2_2") (pintype "input"))
      (node (ref "BLANK1-FIX") (pin "2") (pinfunction "2_2") (pintype "input"))
      (node (ref "BLANK2-NULL") (pin "2") (pinfunction "2_2") (pintype "input"))
      (node (ref "BRT") (pin "2") (pinfunction "2_2") (pintype "input"))
      (node (ref "C") (pin "2") (pinfunction "2_2") (pintype "input"))
      (node (ref "C1") (pin "2") (pinfunction "2_2") (pintype "unspecified"))
      (node (ref "C12") (pin "1") (pinfunction "1_1") (pintype "unspecified"))
      (node (ref "C13") (pin "1") (pinfunction "1_1") (pintype "unspecified"))
      (node (ref "CLR") (pin "2") (pinfunction "2_2") (pintype "input"))
      (node (ref "D") (pin "2") (pinfunction "2_2") (pintype "input"))
      (node (ref "DATA-DES") (pin "2") (pinfunction "2_2") (pintype "input"))
      (node (ref "DIM") (pin "2") (pinfunction "2_2") (pintype "input"))
      (node (ref "DIR-INITREF") (pin "2") (pinfunction "2_2") (pintype "input"))
      (node (ref "DOT") (pin "2") (pinfunction "2_2") (pintype "input"))
      (node (ref "DOWN-NULL") (pin "2") (pinfunction "2_2") (pintype "input"))
      (node (ref "E") (pin "2") (pinfunction "2_2") (pintype "input"))
      (node (ref "F") (pin "2") (pinfunction "2_2") (pintype "input"))
      (node (ref "FPLN-MENU") (pin "2") (pinfunction "2_2") (pintype "input"))
      (node (ref "FUELPRED-DEPARR") (pin "2") (pinfunction "2_2") (pintype "input"))
      (node (ref "G") (pin "2") (pinfunction "2_2") (pintype "input"))
      (node (ref "H") (pin "2") (pinfunction "2_2") (pintype "input"))
      (node (ref "I") (pin "2") (pinfunction "2_2") (pintype "input"))
      (node (ref "INIT-CRZ") (pin "2") (pinfunction "2_2") (pintype "input"))
      (node (ref "J") (pin "2") (pinfunction "2_2") (pintype "input"))
      (node (ref "K") (pin "2") (pinfunction "2_2") (pintype "input"))
      (node (ref "L") (pin "2") (pinfunction "2_2") (pintype "input"))
      (node (ref "LEFT-PREVPAGE") (pin "2") (pinfunction "2_2") (pintype "input"))
      (node (ref "LS1") (pin "2") (pinfunction "2_2") (pintype "input"))
      (node (ref "LS2") (pin "2") (pinfunction "2_2") (pintype "input"))
      (node (ref "LS3") (pin "2") (pinfunction "2_2") (pintype "input"))
      (node (ref "LS4") (pin "2") (pinfunction "2_2") (pintype "input"))
      (node (ref "LS5") (pin "2") (pinfunction "2_2") (pintype "input"))
      (node (ref "LS6") (pin "2") (pinfunction "2_2") (pintype "input"))
      (node (ref "M") (pin "2") (pinfunction "2_2") (pintype "input"))
      (node (ref "MCDUMENU-EXEC") (pin "2") (pinfunction "2_2") (pintype "input"))
      (node (ref "N") (pin "2") (pinfunction "2_2") (pintype "input"))
      (node (ref "O") (pin "2") (pinfunction "2_2") (pintype "input"))
      (node (ref "OUTPUT_SHIFT1") (pin "1") (pinfunction "GND_1") (pintype "passive"))
      (node (ref "OVFY") (pin "2") (pinfunction "2_2") (pintype "input"))
      (node (ref "P") (pin "2") (pinfunction "2_2") (pintype "input"))
      (node (ref "PERF-CLB") (pin "2") (pinfunction "2_2") (pintype "input"))
      (node (ref "PLUSMINUS") (pin "2") (pinfunction "2_2") (pintype "input"))
      (node (ref "PROG-RTE") (pin "2") (pinfunction "2_2") (pintype "input"))
      (node (ref "Q") (pin "2") (pinfunction "2_2") (pintype "input"))
      (node (ref "Q2") (pin "2") (pinfunction "S_2") (pintype "unspecified"))
      (node (ref "R") (pin "2") (pinfunction "2_2") (pintype "input"))
      (node (ref "R7") (pin "1") (pinfunction "1_1") (pintype "input"))
      (node (ref "R8") (pin "2") (pinfunction "2_2") (pintype "input"))
      (node (ref "RADNAV-LEGS") (pin "2") (pinfunction "2_2") (pintype "input"))
      (node (ref "RIGHT-NULL") (pin "2") (pinfunction "2_2") (pintype "input"))
      (node (ref "RS1") (pin "2") (pinfunction "2_2") (pintype "input"))
      (node (ref "RS2") (pin "2") (pinfunction "2_2") (pintype "input"))
      (node (ref "RS3") (pin "2") (pinfunction "2_2") (pintype "input"))
      (node (ref "RS4") (pin "2") (pinfunction "2_2") (pintype "input"))
      (node (ref "RS5") (pin "2") (pinfunction "2_2") (pintype "input"))
      (node (ref "RS6") (pin "2") (pinfunction "2_2") (pintype "input"))
      (node (ref "S") (pin "2") (pinfunction "2_2") (pintype "input"))
      (node (ref "SECFPLN-HOLD") (pin "2") (pinfunction "2_2") (pintype "input"))
      (node (ref "SP") (pin "2") (pinfunction "2_2") (pintype "input"))
      (node (ref "T") (pin "2") (pinfunction "2_2") (pintype "input"))
      (node (ref "U") (pin "2") (pinfunction "2_2") (pintype "input"))
      (node (ref "U1") (pin "43") (pinfunction "GND_43") (pintype "unspecified"))
      (node (ref "U1") (pin "83") (pinfunction "GND_83") (pintype "unspecified"))
      (node (ref "U1") (pin "84") (pinfunction "GND_84") (pintype "unspecified"))
      (node (ref "U18") (pin "15") (pinfunction "CLK/INH_15") (pintype "unspecified"))
      (node (ref "U18") (pin "8") (pinfunction "GND_8") (pintype "unspecified"))
      (node (ref "U19") (pin "10") (pinfunction "SER_10") (pintype "unspecified"))
      (node (ref "U19") (pin "15") (pinfunction "CLK/INH_15") (pintype "unspecified"))
      (node (ref "U19") (pin "8") (pinfunction "GND_8") (pintype "unspecified"))
      (node (ref "UP-NEXTPAGE") (pin "2") (pinfunction "2_2") (pintype "input"))
      (node (ref "V") (pin "2") (pinfunction "2_2") (pintype "input"))
      (node (ref "W") (pin "2") (pinfunction "2_2") (pintype "input"))
      (node (ref "X") (pin "2") (pinfunction "2_2") (pintype "input"))
      (node (ref "Y") (pin "2") (pinfunction "2_2") (pintype "input"))
      (node (ref "Z") (pin "2") (pinfunction "2_2") (pintype "input"))
    )
    (net (code "21") (name "IS_CLOCK") (class "Default")
      (node (ref "U1") (pin "2") (pinfunction "A1_2") (pintype "unspecified"))
      (node (ref "U18") (pin "2") (pinfunction "CLK_2") (pintype "unspecified"))
      (node (ref "U19") (pin "2") (pinfunction "CLK_2") (pintype "unspecified"))
    )
    (net (code "22") (name "IS_DATA") (class "Default")
      (node (ref "U1") (pin "1") (pinfunction "A0_1") (pintype "unspecified"))
      (node (ref "U18") (pin "9") (pinfunction "QH_9") (pintype "unspecified"))
    )
    (net (code "23") (name "IS_LATCH") (class "Default")
      (node (ref "U1") (pin "3") (pinfunction "A2_3") (pintype "unspecified"))
      (node (ref "U18") (pin "1") (pinfunction "SH/LD#_1") (pintype "unspecified"))
      (node (ref "U19") (pin "1") (pinfunction "SH/LD#_1") (pintype "unspecified"))
    )
    (net (code "24") (name "L") (class "Default")
      (node (ref "L") (pin "1") (pinfunction "1_1") (pintype "input"))
      (node (ref "U1") (pin "19") (pinfunction "D34_19") (pintype "unspecified"))
    )
    (net (code "25") (name "L1") (class "Default")
      (node (ref "LS1") (pin "1") (pinfunction "1_1") (pintype "input"))
      (node (ref "RN3") (pin "1") (pinfunction "1_1") (pintype "input"))
      (node (ref "U19") (pin "3") (pinfunction "E_3") (pintype "unspecified"))
    )
    (net (code "26") (name "L2") (class "Default")
      (node (ref "LS2") (pin "1") (pinfunction "1_1") (pintype "input"))
      (node (ref "RN3") (pin "2") (pinfunction "2_2") (pintype "input"))
      (node (ref "U19") (pin "4") (pinfunction "F_4") (pintype "unspecified"))
    )
    (net (code "27") (name "L3") (class "Default")
      (node (ref "LS3") (pin "1") (pinfunction "1_1") (pintype "input"))
      (node (ref "RN3") (pin "3") (pinfunction "3_3") (pintype "input"))
      (node (ref "U19") (pin "5") (pinfunction "G_5") (pintype "unspecified"))
    )
    (net (code "28") (name "L4") (class "Default")
      (node (ref "LS4") (pin "1") (pinfunction "1_1") (pintype "input"))
      (node (ref "RN3") (pin "4") (pinfunction "4_4") (pintype "input"))
      (node (ref "U19") (pin "6") (pinfunction "H_6") (pintype "unspecified"))
    )
    (net (code "29") (name "L5") (class "Default")
      (node (ref "LS5") (pin "1") (pinfunction "1_1") (pintype "input"))
      (node (ref "RN4") (pin "8") (pinfunction "8_8") (pintype "input"))
      (node (ref "U19") (pin "14") (pinfunction "D_14") (pintype "unspecified"))
    )
    (net (code "30") (name "L6") (class "Default")
      (node (ref "LS6") (pin "1") (pinfunction "1_1") (pintype "input"))
      (node (ref "RN4") (pin "7") (pinfunction "7_7") (pintype "input"))
      (node (ref "U19") (pin "13") (pinfunction "C_13") (pintype "unspecified"))
    )
    (net (code "31") (name "LEDDRV_CLK") (class "Default")
      (node (ref "OUTPUT_SHIFT1") (pin "3") (pinfunction "SCLK_3") (pintype "unspecified"))
      (node (ref "U1") (pin "5") (pinfunction "A4_5") (pintype "unspecified"))
    )
    (net (code "32") (name "LEDDRV_DATA") (class "Default")
      (node (ref "OUTPUT_SHIFT1") (pin "2") (pinfunction "SIN_2") (pintype "unspecified"))
      (node (ref "U1") (pin "4") (pinfunction "A3_4") (pintype "unspecified"))
    )
    (net (code "33") (name "LEDDRV_LATCH") (class "Default")
      (node (ref "OUTPUT_SHIFT1") (pin "4") (pinfunction "LAT_4") (pintype "unspecified"))
      (node (ref "U1") (pin "6") (pinfunction "A5_6") (pintype "unspecified"))
    )
    (net (code "34") (name "Left") (class "Default")
      (node (ref "LEFT-PREVPAGE") (pin "1") (pinfunction "1_1") (pintype "input"))
      (node (ref "U1") (pin "74") (pinfunction "D2_74") (pintype "unspecified"))
    )
    (net (code "35") (name "Net-(LED1-Pad1)") (class "Default")
      (node (ref "LED1") (pin "1") (pinfunction "1_1") (pintype "unspecified"))
      (node (ref "LED3") (pin "2") (pinfunction "2_2") (pintype "unspecified"))
    )
    (net (code "36") (name "Net-(LED1-Pad2)") (class "Default")
      (node (ref "LED1") (pin "2") (pinfunction "2_2") (pintype "unspecified"))
      (node (ref "LED2") (pin "1") (pinfunction "1_1") (pintype "unspecified"))
    )
    (net (code "37") (name "Net-(LED3-Pad1)") (class "Default")
      (node (ref "LED3") (pin "1") (pinfunction "1_1") (pintype "unspecified"))
      (node (ref "R16") (pin "1") (pinfunction "1_1") (pintype "input"))
    )
    (net (code "38") (name "Net-(LED4-Pad1)") (class "Default")
      (node (ref "LED4") (pin "1") (pinfunction "1_1") (pintype "unspecified"))
      (node (ref "R15") (pin "1") (pinfunction "1_1") (pintype "input"))
    )
    (net (code "39") (name "Net-(LED4-Pad2)") (class "Default")
      (node (ref "LED4") (pin "2") (pinfunction "2_2") (pintype "unspecified"))
      (node (ref "LED5") (pin "1") (pinfunction "1_1") (pintype "unspecified"))
    )
    (net (code "40") (name "Net-(LED5-Pad2)") (class "Default")
      (node (ref "LED5") (pin "2") (pinfunction "2_2") (pintype "unspecified"))
      (node (ref "LED6") (pin "1") (pinfunction "1_1") (pintype "unspecified"))
    )
    (net (code "41") (name "Net-(LED7-Pad1)") (class "Default")
      (node (ref "LED7") (pin "1") (pinfunction "1_1") (pintype "unspecified"))
      (node (ref "R14") (pin "1") (pinfunction "1_1") (pintype "input"))
    )
    (net (code "42") (name "Net-(LED7-Pad2)") (class "Default")
      (node (ref "LED7") (pin "2") (pinfunction "2_2") (pintype "unspecified"))
      (node (ref "LED8") (pin "1") (pinfunction "1_1") (pintype "unspecified"))
    )
    (net (code "43") (name "Net-(LED8-Pad2)") (class "Default")
      (node (ref "LED8") (pin "2") (pinfunction "2_2") (pintype "unspecified"))
      (node (ref "LED9") (pin "1") (pinfunction "1_1") (pintype "unspecified"))
    )
    (net (code "44") (name "Net-(LED10-Pad1)") (class "Default")
      (node (ref "LED10") (pin "1") (pinfunction "1_1") (pintype "unspecified"))
      (node (ref "R13") (pin "1") (pinfunction "1_1") (pintype "input"))
    )
    (net (code "45") (name "Net-(LED10-Pad2)") (class "Default")
      (node (ref "LED10") (pin "2") (pinfunction "2_2") (pintype "unspecified"))
      (node (ref "LED11") (pin "1") (pinfunction "1_1") (pintype "unspecified"))
    )
    (net (code "46") (name "Net-(LED11-Pad2)") (class "Default")
      (node (ref "LED11") (pin "2") (pinfunction "2_2") (pintype "unspecified"))
      (node (ref "LED12") (pin "1") (pinfunction "1_1") (pintype "unspecified"))
    )
    (net (code "47") (name "Net-(LED13-Pad1)") (class "Default")
      (node (ref "LED13") (pin "1") (pinfunction "1_1") (pintype "unspecified"))
      (node (ref "R12") (pin "1") (pinfunction "1_1") (pintype "input"))
    )
    (net (code "48") (name "Net-(LED13-Pad2)") (class "Default")
      (node (ref "LED13") (pin "2") (pinfunction "2_2") (pintype "unspecified"))
      (node (ref "LED14") (pin "1") (pinfunction "1_1") (pintype "unspecified"))
    )
    (net (code "49") (name "Net-(LED14-Pad2)") (class "Default")
      (node (ref "LED14") (pin "2") (pinfunction "2_2") (pintype "unspecified"))
      (node (ref "LED15") (pin "1") (pinfunction "1_1") (pintype "unspecified"))
    )
    (net (code "50") (name "Net-(LED16-Pad1)") (class "Default")
      (node (ref "LED16") (pin "1") (pinfunction "1_1") (pintype "unspecified"))
      (node (ref "R11") (pin "1") (pinfunction "1_1") (pintype "input"))
    )
    (net (code "51") (name "Net-(LED16-Pad2)") (class "Default")
      (node (ref "LED16") (pin "2") (pinfunction "2_2") (pintype "unspecified"))
      (node (ref "LED17") (pin "1") (pinfunction "1_1") (pintype "unspecified"))
    )
    (net (code "52") (name "Net-(LED17-Pad2)") (class "Default")
      (node (ref "LED17") (pin "2") (pinfunction "2_2") (pintype "unspecified"))
      (node (ref "LED18") (pin "1") (pinfunction "1_1") (pintype "unspecified"))
    )
    (net (code "53") (name "Net-(LED19-Pad1)") (class "Default")
      (node (ref "LED19") (pin "1") (pinfunction "1_1") (pintype "unspecified"))
      (node (ref "R10") (pin "1") (pinfunction "1_1") (pintype "input"))
    )
    (net (code "54") (name "Net-(LED19-Pad2)") (class "Default")
      (node (ref "LED19") (pin "2") (pinfunction "2_2") (pintype "unspecified"))
      (node (ref "LED20") (pin "1") (pinfunction "1_1") (pintype "unspecified"))
    )
    (net (code "55") (name "Net-(LED20-Pad2)") (class "Default")
      (node (ref "LED20") (pin "2") (pinfunction "2_2") (pintype "unspecified"))
      (node (ref "LED21") (pin "1") (pinfunction "1_1") (pintype "unspecified"))
    )
    (net (code "56") (name "Net-(LED22-Pad1)") (class "Default")
      (node (ref "LED22") (pin "1") (pinfunction "1_1") (pintype "unspecified"))
      (node (ref "LED23") (pin "2") (pinfunction "2_2") (pintype "unspecified"))
    )
    (net (code "57") (name "Net-(LED23-Pad1)") (class "Default")
      (node (ref "LED23") (pin "1") (pinfunction "1_1") (pintype "unspecified"))
      (node (ref "LED24") (pin "2") (pinfunction "2_2") (pintype "unspecified"))
    )
    (net (code "58") (name "Net-(LED24-Pad1)") (class "Default")
      (node (ref "LED24") (pin "1") (pinfunction "1_1") (pintype "unspecified"))
      (node (ref "R9") (pin "1") (pinfunction "1_1") (pintype "input"))
    )
    (net (code "59") (name "Net-(LED25-Pad1)") (class "Default")
      (node (ref "LED25") (pin "1") (pinfunction "1_1") (pintype "unspecified"))
      (node (ref "LED26") (pin "2") (pinfunction "2_2") (pintype "unspecified"))
    )
    (net (code "60") (name "Net-(LED26-Pad1)") (class "Default")
      (node (ref "LED26") (pin "1") (pinfunction "1_1") (pintype "unspecified"))
      (node (ref "LED27") (pin "2") (pinfunction "2_2") (pintype "unspecified"))
    )
    (net (code "61") (name "Net-(LED27-Pad1)") (class "Default")
      (node (ref "LED27") (pin "1") (pinfunction "1_1") (pintype "unspecified"))
      (node (ref "R3") (pin "1") (pinfunction "1_1") (pintype "input"))
    )
    (net (code "62") (name "Net-(LED28-Pad1)") (class "Default")
      (node (ref "LED28") (pin "1") (pinfunction "1_1") (pintype "unspecified"))
      (node (ref "LED29") (pin "2") (pinfunction "2_2") (pintype "unspecified"))
    )
    (net (code "63") (name "Net-(LED29-Pad1)") (class "Default")
      (node (ref "LED29") (pin "1") (pinfunction "1_1") (pintype "unspecified"))
      (node (ref "LED30") (pin "2") (pinfunction "2_2") (pintype "unspecified"))
    )
    (net (code "64") (name "Net-(LED30-Pad1)") (class "Default")
      (node (ref "LED30") (pin "1") (pinfunction "1_1") (pintype "unspecified"))
      (node (ref "R2") (pin "1") (pinfunction "1_1") (pintype "input"))
    )
    (net (code "65") (name "Net-(LED31-Pad1)") (class "Default")
      (node (ref "LED31") (pin "1") (pinfunction "1_1") (pintype "unspecified"))
      (node (ref "R1") (pin "1") (pinfunction "1_1") (pintype "input"))
    )
    (net (code "66") (name "Net-(LED31-Pad2)") (class "Default")
      (node (ref "LED31") (pin "2") (pinfunction "2_2") (pintype "unspecified"))
      (node (ref "LED32") (pin "1") (pinfunction "1_1") (pintype "unspecified"))
    )
    (net (code "67") (name "Net-(LED32-Pad2)") (class "Default")
      (node (ref "LED32") (pin "2") (pinfunction "2_2") (pintype "unspecified"))
      (node (ref "LED33") (pin "1") (pinfunction "1_1") (pintype "unspecified"))
    )
    (net (code "68") (name "Net-(OUTPUT_SHIFT1-IREF)") (class "Default")
      (node (ref "OUTPUT_SHIFT1") (pin "23") (pinfunction "IREF_23") (pintype "unspecified"))
      (node (ref "R8") (pin "1") (pinfunction "1_1") (pintype "input"))
    )
    (net (code "69") (name "Net-(Q2-G)") (class "Default")
      (node (ref "Q2") (pin "1") (pinfunction "G_1") (pintype "unspecified"))
      (node (ref "R17") (pin "2") (pinfunction "2_2") (pintype "input"))
      (node (ref "R7") (pin "2") (pinfunction "2_2") (pintype "input"))
    )
    (net (code "70") (name "Net-(U18-SER)") (class "Default")
      (node (ref "U18") (pin "10") (pinfunction "SER_10") (pintype "unspecified"))
      (node (ref "U19") (pin "9") (pinfunction "QH_9") (pintype "unspecified"))
    )
    (net (code "71") (name "R1") (class "Default")
      (node (ref "RS1") (pin "1") (pinfunction "1_1") (pintype "input"))
      (node (ref "U1") (pin "45") (pinfunction "D31_45") (pintype "unspecified"))
    )
    (net (code "72") (name "R2") (class "Default")
      (node (ref "RS2") (pin "1") (pinfunction "1_1") (pintype "input"))
      (node (ref "U1") (pin "46") (pinfunction "D30_46") (pintype "unspecified"))
    )
    (net (code "73") (name "R3") (class "Default")
      (node (ref "RS3") (pin "1") (pinfunction "1_1") (pintype "input"))
      (node (ref "U1") (pin "47") (pinfunction "D29_47") (pintype "unspecified"))
    )
    (net (code "74") (name "R4") (class "Default")
      (node (ref "RS4") (pin "1") (pinfunction "1_1") (pintype "input"))
      (node (ref "U1") (pin "48") (pinfunction "D28_48") (pintype "unspecified"))
    )
    (net (code "75") (name "R5") (class "Default")
      (node (ref "RS5") (pin "1") (pinfunction "1_1") (pintype "input"))
      (node (ref "U1") (pin "49") (pinfunction "D27_49") (pintype "unspecified"))
    )
    (net (code "76") (name "R6") (class "Default")
      (node (ref "RS6") (pin "1") (pinfunction "1_1") (pintype "input"))
      (node (ref "U1") (pin "50") (pinfunction "D26_50") (pintype "unspecified"))
    )
    (net (code "77") (name "Right") (class "Default")
      (node (ref "RIGHT-NULL") (pin "1") (pinfunction "1_1") (pintype "input"))
      (node (ref "U1") (pin "72") (pinfunction "D4_72") (pintype "unspecified"))
    )
    (net (code "78") (name "a") (class "Default")
      (node (ref "A") (pin "1") (pinfunction "1_1") (pintype "input"))
      (node (ref "U1") (pin "65") (pinfunction "D11_65") (pintype "unspecified"))
    )
    (net (code "79") (name "atccomm") (class "Default")
      (node (ref "ATCCOMM-PROG") (pin "1") (pinfunction "1_1") (pintype "input"))
      (node (ref "U1") (pin "58") (pinfunction "D18_58") (pintype "unspecified"))
    )
    (net (code "80") (name "b") (class "Default")
      (node (ref "B") (pin "1") (pinfunction "1_1") (pintype "input"))
      (node (ref "U1") (pin "62") (pinfunction "D14_62") (pintype "unspecified"))
    )
    (net (code "81") (name "blank1") (class "Default")
      (node (ref "BLANK1-FIX") (pin "1") (pinfunction "1_1") (pintype "input"))
      (node (ref "U1") (pin "36") (pinfunction "D51_36") (pintype "unspecified"))
    )
    (net (code "82") (name "blank2") (class "Default")
      (node (ref "BLANK2-NULL") (pin "1") (pinfunction "1_1") (pintype "input"))
      (node (ref "U1") (pin "53") (pinfunction "D23_53") (pintype "unspecified"))
    )
    (net (code "83") (name "brt") (class "Default")
      (node (ref "BRT") (pin "1") (pinfunction "1_1") (pintype "input"))
      (node (ref "U1") (pin "38") (pinfunction "D53_38") (pintype "unspecified"))
    )
    (net (code "84") (name "c") (class "Default")
      (node (ref "C") (pin "1") (pinfunction "1_1") (pintype "input"))
      (node (ref "U1") (pin "61") (pinfunction "D15_61") (pintype "unspecified"))
    )
    (net (code "85") (name "clr") (class "Default")
      (node (ref "CLR") (pin "1") (pinfunction "1_1") (pintype "input"))
      (node (ref "RN5") (pin "8") (pinfunction "8_8") (pintype "input"))
      (node (ref "U18") (pin "14") (pinfunction "D_14") (pintype "unspecified"))
    )
    (net (code "86") (name "d") (class "Default")
      (node (ref "D") (pin "1") (pinfunction "1_1") (pintype "input"))
      (node (ref "U1") (pin "60") (pinfunction "D16_60") (pintype "unspecified"))
    )
    (net (code "87") (name "data") (class "Default")
      (node (ref "DATA-DES") (pin "1") (pinfunction "1_1") (pintype "input"))
      (node (ref "U1") (pin "52") (pinfunction "D24_52") (pintype "unspecified"))
    )
    (net (code "88") (name "dim") (class "Default")
      (node (ref "DIM") (pin "1") (pinfunction "1_1") (pintype "input"))
      (node (ref "U1") (pin "37") (pinfunction "D52_37") (pintype "unspecified"))
    )
    (net (code "89") (name "dot") (class "Default")
      (node (ref "DOT") (pin "1") (pinfunction "1_1") (pintype "input"))
      (node (ref "U1") (pin "12") (pinfunction "A11_12") (pintype "unspecified"))
    )
    (net (code "90") (name "e") (class "Default")
      (node (ref "E") (pin "1") (pinfunction "1_1") (pintype "input"))
      (node (ref "U1") (pin "59") (pinfunction "D17_59") (pintype "unspecified"))
    )
    (net (code "91") (name "exec") (class "Default")
      (node (ref "EXEC") (pin "1") (pinfunction "K_1") (pintype "unspecified"))
      (node (ref "OUTPUT_SHIFT1") (pin "15") (pinfunction "OUT10_15") (pintype "output"))
    )
    (net (code "92") (name "f") (class "Default")
      (node (ref "F") (pin "1") (pinfunction "1_1") (pintype "input"))
      (node (ref "U1") (pin "15") (pinfunction "A14_15") (pintype "unspecified"))
    )
    (net (code "93") (name "fuelpred") (class "Default")
      (node (ref "FUELPRED-DEPARR") (pin "1") (pinfunction "1_1") (pintype "input"))
      (node (ref "U1") (pin "54") (pinfunction "D22_54") (pintype "unspecified"))
    )
    (net (code "94") (name "g") (class "Default")
      (node (ref "G") (pin "1") (pinfunction "1_1") (pintype "input"))
      (node (ref "U1") (pin "16") (pinfunction "A15_16") (pintype "unspecified"))
    )
    (net (code "95") (name "h") (class "Default")
      (node (ref "H") (pin "1") (pinfunction "1_1") (pintype "input"))
      (node (ref "U1") (pin "17") (pinfunction "D32_17") (pintype "unspecified"))
    )
    (net (code "96") (name "i") (class "Default")
      (node (ref "I") (pin "1") (pinfunction "1_1") (pintype "input"))
      (node (ref "U1") (pin "34") (pinfunction "D49_34") (pintype "unspecified"))
    )
    (net (code "97") (name "indicator1") (class "Default")
      (node (ref "INDICATOR1") (pin "1") (pinfunction "K_1") (pintype "unspecified"))
      (node (ref "OUTPUT_SHIFT1") (pin "5") (pinfunction "OUT0_5") (pintype "output"))
    )
    (net (code "98") (name "indicator2") (class "Default")
      (node (ref "INDICATOR2") (pin "1") (pinfunction "K_1") (pintype "unspecified"))
      (node (ref "OUTPUT_SHIFT1") (pin "6") (pinfunction "OUT1_6") (pintype "output"))
    )
    (net (code "99") (name "indicator3") (class "Default")
      (node (ref "INDICATOR3") (pin "1") (pinfunction "K_1") (pintype "unspecified"))
      (node (ref "OUTPUT_SHIFT1") (pin "7") (pinfunction "OUT2_7") (pintype "output"))
    )
    (net (code "100") (name "indicator4") (class "Default")
      (node (ref "INDICATOR4") (pin "1") (pinfunction "K_1") (pintype "unspecified"))
      (node (ref "OUTPUT_SHIFT1") (pin "8") (pinfunction "OUT3_8") (pintype "output"))
    )
    (net (code "101") (name "indicator5") (class "Default")
      (node (ref "INDICATOR5") (pin "1") (pinfunction "K_1") (pintype "unspecified"))
      (node (ref "OUTPUT_SHIFT1") (pin "9") (pinfunction "OUT4_9") (pintype "output"))
    )
    (net (code "102") (name "indicator6") (class "Default")
      (node (ref "INDICATOR6") (pin "2") (pinfunction "K_2") (pintype "unspecified"))
      (node (ref "OUTPUT_SHIFT1") (pin "10") (pinfunction "OUT5_10") (pintype "output"))
    )
    (net (code "103") (name "indicator6a") (class "Default")
      (node (ref "INDICATOR6A") (pin "2") (pinfunction "K_2") (pintype "unspecified"))
      (node (ref "OUTPUT_SHIFT1") (pin "11") (pinfunction "OUT6_11") (pintype "output"))
    )
    (net (code "104") (name "indicator7") (class "Default")
      (node (ref "INDICATOR7") (pin "1") (pinfunction "K_1") (pintype "unspecified"))
      (node (ref "OUTPUT_SHIFT1") (pin "12") (pinfunction "OUT7_12") (pintype "output"))
    )
    (net (code "105") (name "indicator8") (class "Default")
      (node (ref "INDICATOR8") (pin "1") (pinfunction "K_1") (pintype "unspecified"))
      (node (ref "OUTPUT_SHIFT1") (pin "13") (pinfunction "OUT8_13") (pintype "output"))
    )
    (net (code "106") (name "indicator9") (class "Default")
      (node (ref "INDICATOR9") (pin "1") (pinfunction "K_1") (pintype "unspecified"))
      (node (ref "OUTPUT_SHIFT1") (pin "14") (pinfunction "OUT9_14") (pintype "output"))
    )
    (net (code "107") (name "init") (class "Default")
      (node (ref "INIT-CRZ") (pin "1") (pinfunction "1_1") (pintype "input"))
      (node (ref "U1") (pin "35") (pinfunction "D50_35") (pintype "unspecified"))
    )
    (net (code "108") (name "j") (class "Default")
      (node (ref "J") (pin "1") (pinfunction "1_1") (pintype "input"))
      (node (ref "U1") (pin "33") (pinfunction "D48_33") (pintype "unspecified"))
    )
    (net (code "109") (name "k") (class "Default")
      (node (ref "K") (pin "1") (pinfunction "1_1") (pintype "input"))
      (node (ref "U1") (pin "18") (pinfunction "D33_18") (pintype "unspecified"))
    )
    (net (code "110") (name "m") (class "Default")
      (node (ref "M") (pin "1") (pinfunction "1_1") (pintype "input"))
      (node (ref "U1") (pin "20") (pinfunction "D35_20") (pintype "unspecified"))
    )
    (net (code "111") (name "mcdumenu") (class "Default")
      (node (ref "MCDUMENU-EXEC") (pin "1") (pinfunction "1_1") (pintype "input"))
      (node (ref "U1") (pin "51") (pinfunction "D25_51") (pintype "unspecified"))
    )
    (net (code "112") (name "n") (class "Default")
      (node (ref "N") (pin "1") (pinfunction "1_1") (pintype "input"))
      (node (ref "RN6") (pin "1") (pinfunction "1_1") (pintype "input"))
      (node (ref "U18") (pin "3") (pinfunction "E_3") (pintype "unspecified"))
    )
    (net (code "113") (name "o") (class "Default")
      (node (ref "O") (pin "1") (pinfunction "1_1") (pintype "input"))
      (node (ref "RN6") (pin "2") (pinfunction "2_2") (pintype "input"))
      (node (ref "U18") (pin "4") (pinfunction "F_4") (pintype "unspecified"))
    )
    (net (code "114") (name "ovfy") (class "Default")
      (node (ref "OVFY") (pin "1") (pinfunction "1_1") (pintype "input"))
      (node (ref "RN5") (pin "6") (pinfunction "6_6") (pintype "input"))
      (node (ref "U18") (pin "12") (pinfunction "B_12") (pintype "unspecified"))
    )
    (net (code "115") (name "p") (class "Default")
      (node (ref "P") (pin "1") (pinfunction "1_1") (pintype "input"))
      (node (ref "U1") (pin "22") (pinfunction "D37_22") (pintype "unspecified"))
    )
    (net (code "116") (name "perf") (class "Default")
      (node (ref "PERF-CLB") (pin "1") (pinfunction "1_1") (pintype "input"))
      (node (ref "U1") (pin "55") (pinfunction "D21_55") (pintype "unspecified"))
    )
    (net (code "117") (name "plusminus") (class "Default")
      (node (ref "PLUSMINUS") (pin "1") (pinfunction "1_1") (pintype "input"))
      (node (ref "U1") (pin "14") (pinfunction "A13_14") (pintype "unspecified"))
    )
    (net (code "118") (name "prog") (class "Default")
      (node (ref "PROG-RTE") (pin "1") (pinfunction "1_1") (pintype "input"))
      (node (ref "U1") (pin "57") (pinfunction "D19_57") (pintype "unspecified"))
    )
    (net (code "119") (name "q") (class "Default")
      (node (ref "Q") (pin "1") (pinfunction "1_1") (pintype "input"))
      (node (ref "U1") (pin "23") (pinfunction "D38_23") (pintype "unspecified"))
    )
    (net (code "120") (name "r") (class "Default")
      (node (ref "R") (pin "1") (pinfunction "1_1") (pintype "input"))
      (node (ref "U1") (pin "24") (pinfunction "D39_24") (pintype "unspecified"))
    )
    (net (code "121") (name "radnav") (class "Default")
      (node (ref "RADNAV-LEGS") (pin "1") (pinfunction "1_1") (pintype "input"))
      (node (ref "U1") (pin "56") (pinfunction "D20_56") (pintype "unspecified"))
    )
    (net (code "122") (name "s") (class "Default")
      (node (ref "RN6") (pin "3") (pinfunction "3_3") (pintype "input"))
      (node (ref "S") (pin "1") (pinfunction "1_1") (pintype "input"))
      (node (ref "U18") (pin "5") (pinfunction "G_5") (pintype "unspecified"))
    )
    (net (code "123") (name "secfpln") (class "Default")
      (node (ref "SECFPLN-HOLD") (pin "1") (pinfunction "1_1") (pintype "input"))
      (node (ref "U1") (pin "21") (pinfunction "D36_21") (pintype "unspecified"))
    )
    (net (code "124") (name "sp") (class "Default")
      (node (ref "SP") (pin "1") (pinfunction "1_1") (pintype "input"))
      (node (ref "U1") (pin "32") (pinfunction "D47_32") (pintype "unspecified"))
    )
    (net (code "125") (name "t") (class "Default")
      (node (ref "RN6") (pin "4") (pinfunction "4_4") (pintype "input"))
      (node (ref "T") (pin "1") (pinfunction "1_1") (pintype "input"))
      (node (ref "U18") (pin "6") (pinfunction "H_6") (pintype "unspecified"))
    )
    (net (code "126") (name "u") (class "Default")
      (node (ref "U") (pin "1") (pinfunction "1_1") (pintype "input"))
      (node (ref "U1") (pin "26") (pinfunction "D41_26") (pintype "unspecified"))
    )
    (net (code "127") (name "unconnected-(OUTPUT_SHIFT1-OUT11-Pad16)") (class "Default")
      (node (ref "OUTPUT_SHIFT1") (pin "16") (pinfunction "OUT11_16") (pintype "output+no_connect"))
    )
    (net (code "128") (name "unconnected-(OUTPUT_SHIFT1-OUT12-Pad17)") (class "Default")
      (node (ref "OUTPUT_SHIFT1") (pin "17") (pinfunction "OUT12_17") (pintype "output+no_connect"))
    )
    (net (code "129") (name "unconnected-(OUTPUT_SHIFT1-OUT13-Pad18)") (class "Default")
      (node (ref "OUTPUT_SHIFT1") (pin "18") (pinfunction "OUT13_18") (pintype "output+no_connect"))
    )
    (net (code "130") (name "unconnected-(OUTPUT_SHIFT1-OUT14-Pad19)") (class "Default")
      (node (ref "OUTPUT_SHIFT1") (pin "19") (pinfunction "OUT14_19") (pintype "output+no_connect"))
    )
    (net (code "131") (name "unconnected-(OUTPUT_SHIFT1-OUT15-Pad20)") (class "Default")
      (node (ref "OUTPUT_SHIFT1") (pin "20") (pinfunction "OUT15_20") (pintype "output+no_connect"))
    )
    (net (code "132") (name "unconnected-(OUTPUT_SHIFT1-SOUT-Pad22)") (class "Default")
      (node (ref "OUTPUT_SHIFT1") (pin "22") (pinfunction "SOUT_22") (pintype "output+no_connect"))
    )
    (net (code "133") (name "unconnected-(U1-3.3V-Pad79)") (class "Default")
      (node (ref "U1") (pin "79") (pinfunction "3.3V_79") (pintype "unspecified+no_connect"))
    )
    (net (code "134") (name "unconnected-(U1-3.3V-Pad80)") (class "Default")
      (node (ref "U1") (pin "80") (pinfunction "3.3V_80") (pintype "unspecified+no_connect"))
    )
    (net (code "135") (name "unconnected-(U1-A6-Pad7)") (class "Default")
      (node (ref "U1") (pin "7") (pinfunction "A6_7") (pintype "unspecified+no_connect"))
    )
    (net (code "136") (name "unconnected-(U1-AREF-Pad78)") (class "Default")
      (node (ref "U1") (pin "78") (pinfunction "AREF_78") (pintype "unspecified+no_connect"))
    )
    (net (code "137") (name "unconnected-(U1-D44-Pad29)") (class "Default")
      (node (ref "U1") (pin "29") (pinfunction "D44_29") (pintype "unspecified+no_connect"))
    )
    (net (code "138") (name "unconnected-(U1-MISO-Pad40)") (class "Default")
      (node (ref "U1") (pin "40") (pinfunction "MISO_40") (pintype "unspecified+no_connect"))
    )
    (net (code "139") (name "unconnected-(U1-MOSI-Pad41)") (class "Default")
      (node (ref "U1") (pin "41") (pinfunction "MOSI_41") (pintype "unspecified+no_connect"))
    )
    (net (code "140") (name "unconnected-(U1-RX-Pad76)") (class "Default")
      (node (ref "U1") (pin "76") (pinfunction "RX_76") (pintype "unspecified+no_connect"))
    )
    (net (code "141") (name "unconnected-(U1-Reset-Pad44)") (class "Default")
      (node (ref "U1") (pin "44") (pinfunction "Reset_44") (pintype "unspecified+no_connect"))
    )
    (net (code "142") (name "unconnected-(U1-Reset-Pad77)") (class "Default")
      (node (ref "U1") (pin "77") (pinfunction "Reset_77") (pintype "unspecified+no_connect"))
    )
    (net (code "143") (name "unconnected-(U1-SCK-Pad42)") (class "Default")
      (node (ref "U1") (pin "42") (pinfunction "SCK_42") (pintype "unspecified+no_connect"))
    )
    (net (code "144") (name "unconnected-(U1-TX-Pad75)") (class "Default")
      (node (ref "U1") (pin "75") (pinfunction "TX_75") (pintype "unspecified+no_connect"))
    )
    (net (code "145") (name "unconnected-(U1-VIN-Pad85)") (class "Default")
      (node (ref "U1") (pin "85") (pinfunction "VIN_85") (pintype "unspecified+no_connect"))
    )
    (net (code "146") (name "unconnected-(U1-VIN-Pad86)") (class "Default")
      (node (ref "U1") (pin "86") (pinfunction "VIN_86") (pintype "unspecified+no_connect"))
    )
    (net (code "147") (name "unconnected-(U18-QH#-Pad7)") (class "Default")
      (node (ref "U18") (pin "7") (pinfunction "QH#_7") (pintype "unspecified+no_connect"))
    )
    (net (code "148") (name "unconnected-(U19-QH#-Pad7)") (class "Default")
      (node (ref "U19") (pin "7") (pinfunction "QH#_7") (pintype "unspecified+no_connect"))
    )
    (net (code "149") (name "up") (class "Default")
      (node (ref "U1") (pin "73") (pinfunction "D3_73") (pintype "unspecified"))
      (node (ref "UP-NEXTPAGE") (pin "1") (pinfunction "1_1") (pintype "input"))
    )
    (net (code "150") (name "v") (class "Default")
      (node (ref "U1") (pin "27") (pinfunction "D42_27") (pintype "unspecified"))
      (node (ref "V") (pin "1") (pinfunction "1_1") (pintype "input"))
    )
    (net (code "151") (name "w") (class "Default")
      (node (ref "U1") (pin "28") (pinfunction "D43_28") (pintype "unspecified"))
      (node (ref "W") (pin "1") (pinfunction "1_1") (pintype "input"))
    )
    (net (code "152") (name "x") (class "Default")
      (node (ref "RN5") (pin "5") (pinfunction "5_5") (pintype "input"))
      (node (ref "U18") (pin "11") (pinfunction "A_11") (pintype "unspecified"))
      (node (ref "X") (pin "1") (pinfunction "1_1") (pintype "input"))
    )
    (net (code "153") (name "y") (class "Default")
      (node (ref "RN5") (pin "7") (pinfunction "7_7") (pintype "input"))
      (node (ref "U18") (pin "13") (pinfunction "C_13") (pintype "unspecified"))
      (node (ref "Y") (pin "1") (pinfunction "1_1") (pintype "input"))
    )
    (net (code "154") (name "z") (class "Default")
      (node (ref "U1") (pin "30") (pinfunction "D45_30") (pintype "unspecified"))
      (node (ref "Z") (pin "1") (pinfunction "1_1") (pintype "input"))
    )
    (net (code "155") (name "{slash}") (class "Default")
      (node (ref "/") (pin "1") (pinfunction "1_1") (pintype "input"))
      (node (ref "U1") (pin "31") (pinfunction "D46_31") (pintype "unspecified"))
    )
  )
)
